# NvideaJetsonPeripherals.net
KiCad netlist of a schematic drawn in Altium Designer
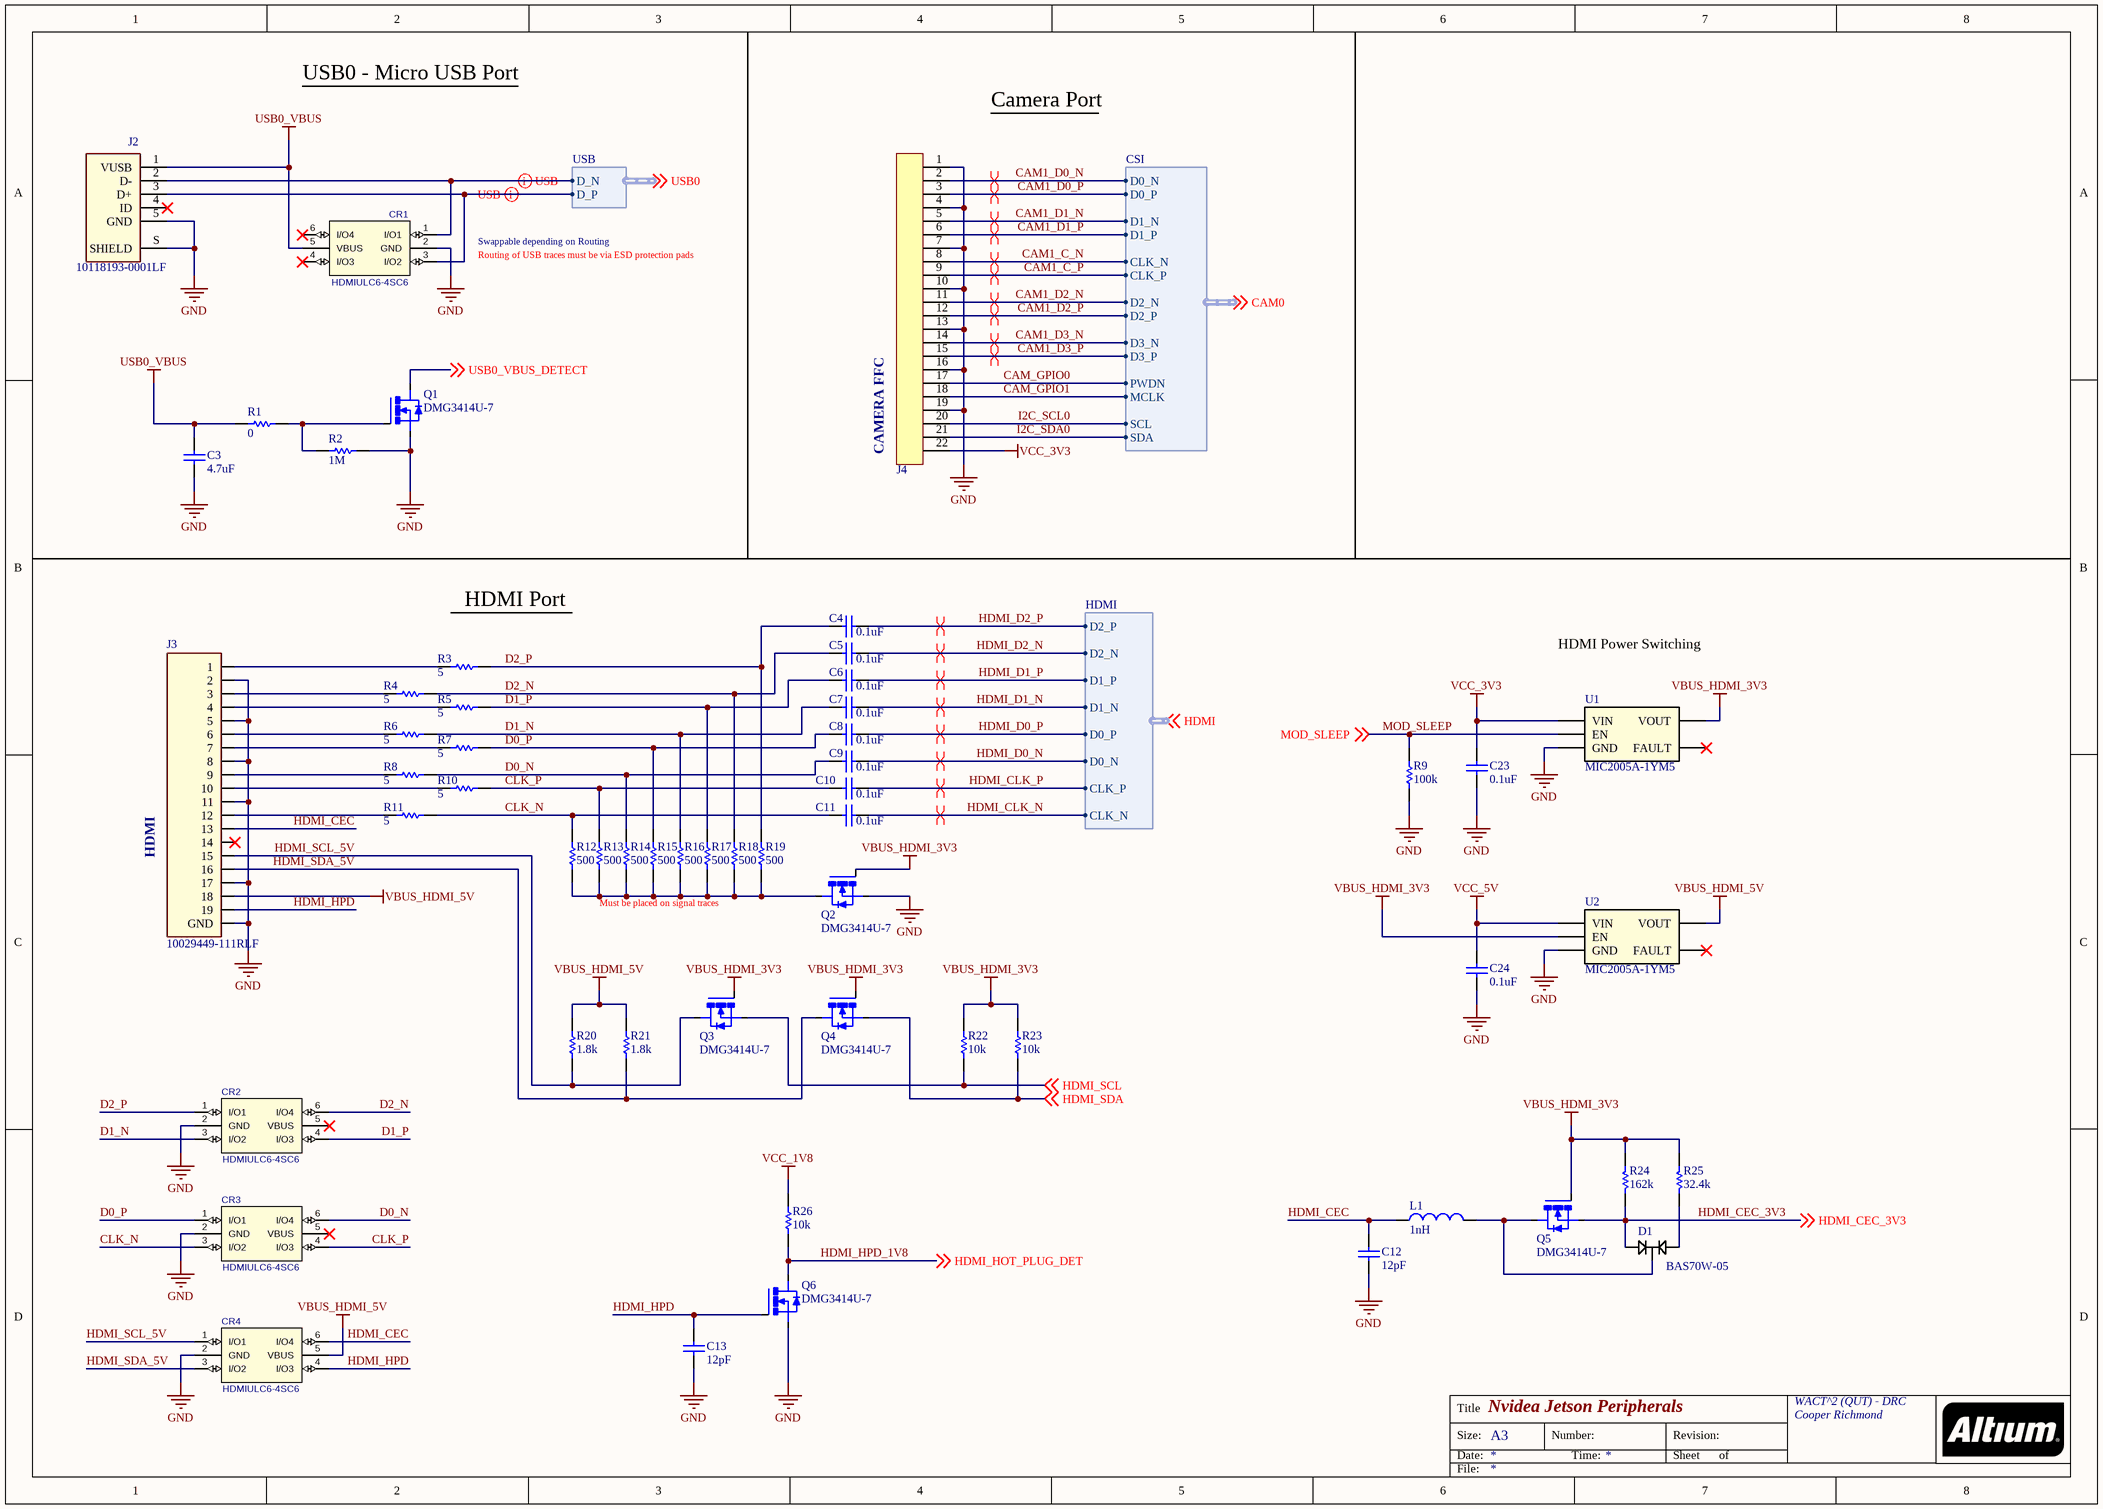
[diagram p0: NvideaJetsonPeripherals.SchDoc]

(export (version "E")
  (design (tool "Eeschema 10.0.6"))
  (components
    (comp (ref "C3")
      (value "4.7uF")
      (footprint "CASE-A")
      (description "=Description")
      (fields (field (name "Comment") "CAP"))
      (libsource (lib "DRClib") (part "CAP"))
    )
    (comp (ref "C4")
      (value "0.1uF")
      (footprint "C0402")
      (description "=Description")
      (fields (field (name "Comment") "CAP"))
      (libsource (lib "DRClib") (part "CAP"))
    )
    (comp (ref "C5")
      (value "0.1uF")
      (footprint "C0402")
      (description "=Description")
      (fields (field (name "Comment") "CAP"))
      (libsource (lib "DRClib") (part "CAP"))
    )
    (comp (ref "C6")
      (value "0.1uF")
      (footprint "C0402")
      (description "=Description")
      (fields (field (name "Comment") "CAP"))
      (libsource (lib "DRClib") (part "CAP"))
    )
    (comp (ref "C7")
      (value "0.1uF")
      (footprint "C0402")
      (description "=Description")
      (fields (field (name "Comment") "CAP"))
      (libsource (lib "DRClib") (part "CAP"))
    )
    (comp (ref "C8")
      (value "0.1uF")
      (footprint "C0402")
      (description "=Description")
      (fields (field (name "Comment") "CAP"))
      (libsource (lib "DRClib") (part "CAP"))
    )
    (comp (ref "C9")
      (value "0.1uF")
      (footprint "C0402")
      (description "=Description")
      (fields (field (name "Comment") "CAP"))
      (libsource (lib "DRClib") (part "CAP"))
    )
    (comp (ref "C10")
      (value "0.1uF")
      (footprint "C0402")
      (description "=Description")
      (fields (field (name "Comment") "CAP"))
      (libsource (lib "DRClib") (part "CAP"))
    )
    (comp (ref "C11")
      (value "0.1uF")
      (footprint "C0402")
      (description "=Description")
      (fields (field (name "Comment") "CAP"))
      (libsource (lib "DRClib") (part "CAP"))
    )
    (comp (ref "C12")
      (value "12pF")
      (footprint "C0402")
      (description "=Description")
      (fields (field (name "Comment") "CAP"))
      (libsource (lib "DRClib") (part "CAP"))
    )
    (comp (ref "C13")
      (value "12pF")
      (footprint "C0402")
      (description "=Description")
      (fields (field (name "Comment") "CAP"))
      (libsource (lib "DRClib") (part "CAP"))
    )
    (comp (ref "C23")
      (value "0.1uF")
      (footprint "C0402")
      (description "=Description")
      (fields (field (name "Comment") "CAP"))
      (libsource (lib "DRClib") (part "CAP"))
    )
    (comp (ref "C24")
      (value "0.1uF")
      (footprint "C0402")
      (description "=Description")
      (fields (field (name "Comment") "CAP"))
      (libsource (lib "DRClib") (part "CAP"))
    )
    (comp (ref "CR1")
      (value "HDMIULC6-4SC6")
      (footprint "SOT23-6L")
      (libsource (lib "") (part "HDMIULC6-4SC6_1"))
    )
    (comp (ref "CR2")
      (value "HDMIULC6-4SC6")
      (footprint "SOT23-6L")
      (libsource (lib "DRClib") (part "HDMIULC6-4SC6"))
    )
    (comp (ref "CR3")
      (value "HDMIULC6-4SC6")
      (footprint "SOT23-6L")
      (libsource (lib "DRClib") (part "HDMIULC6-4SC6"))
    )
    (comp (ref "CR4")
      (value "HDMIULC6-4SC6")
      (footprint "SOT23-6L")
      (libsource (lib "DRClib") (part "HDMIULC6-4SC6"))
    )
    (comp (ref "D1")
      (value "BAS70W-05")
      (footprint "SOT323-3")
      (description "SURFACE MOUNT SCHOTTKY BARRIER DIODE")
      (libsource (lib "DRClib") (part "BAS70W-05"))
    )
    (comp (ref "J2")
      (value "10118193-0001LF")
      (footprint "10118193-0001LF")
      (description "Single Port 5 Contact Shielded SMT MICRO USB B-Type Receptacle")
      (fields (field (name "MF") "Amphenol ICC") (field (name "DIGI-KEY_PART_NUMBER") "609-4616-1-ND"))
      (libsource (lib "DRClib") (part "10118193-0001LF"))
    )
    (comp (ref "J3")
      (value "10029449-111RLF")
      (footprint "10029449-111RLF")
      (description "CONN RCPT 1.4 HDMI 19POS R/A")
      (libsource (lib "DRClib") (part "10029449-111RLF"))
    )
    (comp (ref "J4")
      (value "5019512210")
      (footprint "5019512210")
      (description "FFC 22 POS VERT")
      (libsource (lib "Header") (part "HDR_1x22"))
    )
    (comp (ref "L1")
      (value "1nH")
      (footprint "L0402")
      (description "=Description")
      (fields (field (name "Comment") "IND"))
      (libsource (lib "DRClib") (part "IND"))
    )
    (comp (ref "Q1")
      (value "DMG3414U-7")
      (footprint "SOT23-3")
      (description "=Description")
      (libsource (lib "") (part "MOSFET_N_GSD_1"))
    )
    (comp (ref "Q2")
      (value "DMG3414U-7")
      (footprint "SOT23-3")
      (description "=Description")
      (libsource (lib "DRClib") (part "MOSFET_N_GSD"))
    )
    (comp (ref "Q3")
      (value "DMG3414U-7")
      (footprint "SOT23-3")
      (description "=Description")
      (libsource (lib "DRClib") (part "MOSFET_N_GSD"))
    )
    (comp (ref "Q4")
      (value "DMG3414U-7")
      (footprint "SOT23-3")
      (description "=Description")
      (libsource (lib "DRClib") (part "MOSFET_N_GSD"))
    )
    (comp (ref "Q5")
      (value "DMG3414U-7")
      (footprint "SOT23-3")
      (description "N Channel MOSFET, SOT23")
      (libsource (lib "DRClib") (part "MOSFET_N_GSD"))
    )
    (comp (ref "Q6")
      (value "DMG3414U-7")
      (footprint "SOT23-3")
      (description "N Channel MOSFET, SOT23")
      (libsource (lib "") (part "MOSFET_N_GSD_1"))
    )
    (comp (ref "R1")
      (value "0")
      (footprint "R0402")
      (description "=Description")
      (fields (field (name "Comment") "RES"))
      (libsource (lib "DRClib") (part "RES"))
    )
    (comp (ref "R2")
      (value "1M")
      (footprint "R0402")
      (description "=Description")
      (fields (field (name "Comment") "RES"))
      (libsource (lib "DRClib") (part "RES"))
    )
    (comp (ref "R3")
      (value "5")
      (footprint "R0402")
      (description "=Description")
      (fields (field (name "Comment") "RES"))
      (libsource (lib "DRClib") (part "RES"))
    )
    (comp (ref "R4")
      (value "5")
      (footprint "R0402")
      (description "=Description")
      (fields (field (name "Comment") "RES"))
      (libsource (lib "DRClib") (part "RES"))
    )
    (comp (ref "R5")
      (value "5")
      (footprint "R0402")
      (description "=Description")
      (fields (field (name "Comment") "RES"))
      (libsource (lib "DRClib") (part "RES"))
    )
    (comp (ref "R6")
      (value "5")
      (footprint "R0402")
      (description "=Description")
      (fields (field (name "Comment") "RES"))
      (libsource (lib "DRClib") (part "RES"))
    )
    (comp (ref "R7")
      (value "5")
      (footprint "R0402")
      (description "=Description")
      (fields (field (name "Comment") "RES"))
      (libsource (lib "DRClib") (part "RES"))
    )
    (comp (ref "R8")
      (value "5")
      (footprint "R0402")
      (description "=Description")
      (fields (field (name "Comment") "RES"))
      (libsource (lib "DRClib") (part "RES"))
    )
    (comp (ref "R9")
      (value "100k")
      (footprint "R0402")
      (description "=Description")
      (fields (field (name "Comment") "RES"))
      (libsource (lib "DRClib") (part "RES"))
    )
    (comp (ref "R10")
      (value "5")
      (footprint "R0402")
      (description "=Description")
      (fields (field (name "Comment") "RES"))
      (libsource (lib "DRClib") (part "RES"))
    )
    (comp (ref "R11")
      (value "5")
      (footprint "R0402")
      (description "=Description")
      (fields (field (name "Comment") "RES"))
      (libsource (lib "DRClib") (part "RES"))
    )
    (comp (ref "R12")
      (value "500")
      (footprint "R0402")
      (description "=Description")
      (fields (field (name "Comment") "RES"))
      (libsource (lib "DRClib") (part "RES"))
    )
    (comp (ref "R13")
      (value "500")
      (footprint "R0402")
      (description "=Description")
      (fields (field (name "Comment") "RES"))
      (libsource (lib "DRClib") (part "RES"))
    )
    (comp (ref "R14")
      (value "500")
      (footprint "R0402")
      (description "=Description")
      (fields (field (name "Comment") "RES"))
      (libsource (lib "DRClib") (part "RES"))
    )
    (comp (ref "R15")
      (value "500")
      (footprint "R0402")
      (description "=Description")
      (fields (field (name "Comment") "RES"))
      (libsource (lib "DRClib") (part "RES"))
    )
    (comp (ref "R16")
      (value "500")
      (footprint "R0402")
      (description "=Description")
      (fields (field (name "Comment") "RES"))
      (libsource (lib "DRClib") (part "RES"))
    )
    (comp (ref "R17")
      (value "500")
      (footprint "R0402")
      (description "=Description")
      (fields (field (name "Comment") "RES"))
      (libsource (lib "DRClib") (part "RES"))
    )
    (comp (ref "R18")
      (value "500")
      (footprint "R0402")
      (description "=Description")
      (fields (field (name "Comment") "RES"))
      (libsource (lib "DRClib") (part "RES"))
    )
    (comp (ref "R19")
      (value "500")
      (footprint "R0402")
      (description "=Description")
      (fields (field (name "Comment") "RES"))
      (libsource (lib "DRClib") (part "RES"))
    )
    (comp (ref "R20")
      (value "1.8k")
      (footprint "R0402")
      (description "=Description")
      (fields (field (name "Comment") "RES"))
      (libsource (lib "DRClib") (part "RES"))
    )
    (comp (ref "R21")
      (value "1.8k")
      (footprint "R0402")
      (description "=Description")
      (fields (field (name "Comment") "RES"))
      (libsource (lib "DRClib") (part "RES"))
    )
    (comp (ref "R22")
      (value "10k")
      (footprint "R0402")
      (description "=Description")
      (fields (field (name "Comment") "RES"))
      (libsource (lib "DRClib") (part "RES"))
    )
    (comp (ref "R23")
      (value "10k")
      (footprint "R0402")
      (description "=Description")
      (fields (field (name "Comment") "RES"))
      (libsource (lib "DRClib") (part "RES"))
    )
    (comp (ref "R24")
      (value "162k")
      (footprint "R0402")
      (description "=Description")
      (fields (field (name "Comment") "RES"))
      (libsource (lib "DRClib") (part "RES"))
    )
    (comp (ref "R25")
      (value "32.4k")
      (footprint "R0402")
      (description "=Description")
      (fields (field (name "Comment") "RES"))
      (libsource (lib "DRClib") (part "RES"))
    )
    (comp (ref "R26")
      (value "10k")
      (footprint "R0402")
      (description "=Description")
      (fields (field (name "Comment") "RES"))
      (libsource (lib "DRClib") (part "RES"))
    )
    (comp (ref "U1")
      (value "MIC2005A-1YM5")
      (footprint "SOT23-5")
      (description "Power Switch/Driver 1:1 P-Channel 500mA SOT-23-5")
      (libsource (lib "DRClib") (part "MIC2005A-1YM5"))
    )
    (comp (ref "U2")
      (value "MIC2005A-1YM5")
      (footprint "SOT23-5")
      (description "Power Switch/Driver 1:1 P-Channel 500mA SOT-23-5")
      (libsource (lib "DRClib") (part "MIC2005A-1YM5"))
    )
  )
  (nets
    (net (code "1") (name "/CAM1_C_N") (class "Default")
      (node (ref "J4") (pin "8") (pinfunction "8_8") (pintype "passive"))
    )
    (net (code "2") (name "/CAM1_C_P") (class "Default")
      (node (ref "J4") (pin "9") (pinfunction "9_9") (pintype "passive"))
    )
    (net (code "3") (name "/CAM1_D0_N") (class "Default")
      (node (ref "J4") (pin "2") (pinfunction "2_2") (pintype "passive"))
    )
    (net (code "4") (name "/CAM1_D0_P") (class "Default")
      (node (ref "J4") (pin "3") (pinfunction "3_3") (pintype "passive"))
    )
    (net (code "5") (name "/CAM1_D1_N") (class "Default")
      (node (ref "J4") (pin "5") (pinfunction "5_5") (pintype "passive"))
    )
    (net (code "6") (name "/CAM1_D1_P") (class "Default")
      (node (ref "J4") (pin "6") (pinfunction "6_6") (pintype "passive"))
    )
    (net (code "7") (name "/CAM1_D2_N") (class "Default")
      (node (ref "J4") (pin "11") (pinfunction "11_11") (pintype "passive"))
    )
    (net (code "8") (name "/CAM1_D2_P") (class "Default")
      (node (ref "J4") (pin "12") (pinfunction "12_12") (pintype "passive"))
    )
    (net (code "9") (name "/CAM1_D3_N") (class "Default")
      (node (ref "J4") (pin "14") (pinfunction "14_14") (pintype "passive"))
    )
    (net (code "10") (name "/CAM1_D3_P") (class "Default")
      (node (ref "J4") (pin "15") (pinfunction "15_15") (pintype "passive"))
    )
    (net (code "11") (name "/CAM_GPIO0") (class "Default")
      (node (ref "J4") (pin "17") (pinfunction "17_17") (pintype "passive"))
    )
    (net (code "12") (name "/CAM_GPIO1") (class "Default")
      (node (ref "J4") (pin "18") (pinfunction "18_18") (pintype "passive"))
    )
    (net (code "13") (name "/CLK_N") (class "Default")
      (node (ref "C11") (pin "1") (pinfunction "1_1") (pintype "passive"))
      (node (ref "CR3") (pin "3") (pinfunction "I/O2_3") (pintype "bidirectional"))
      (node (ref "R11") (pin "2") (pinfunction "2_2") (pintype "passive"))
      (node (ref "R12") (pin "1") (pinfunction "1_1") (pintype "passive"))
    )
    (net (code "14") (name "/CLK_P") (class "Default")
      (node (ref "C10") (pin "1") (pinfunction "1_1") (pintype "passive"))
      (node (ref "CR3") (pin "4") (pinfunction "I/O3_4") (pintype "bidirectional"))
      (node (ref "R10") (pin "2") (pinfunction "2_2") (pintype "passive"))
      (node (ref "R13") (pin "1") (pinfunction "1_1") (pintype "passive"))
    )
    (net (code "15") (name "/D0_N") (class "Default")
      (node (ref "C9") (pin "1") (pinfunction "1_1") (pintype "passive"))
      (node (ref "CR3") (pin "6") (pinfunction "I/O4_6") (pintype "bidirectional"))
      (node (ref "R14") (pin "1") (pinfunction "1_1") (pintype "passive"))
      (node (ref "R8") (pin "2") (pinfunction "2_2") (pintype "passive"))
    )
    (net (code "16") (name "/D0_P") (class "Default")
      (node (ref "C8") (pin "1") (pinfunction "1_1") (pintype "passive"))
      (node (ref "CR3") (pin "1") (pinfunction "I/O1_1") (pintype "bidirectional"))
      (node (ref "R15") (pin "1") (pinfunction "1_1") (pintype "passive"))
      (node (ref "R7") (pin "2") (pinfunction "2_2") (pintype "passive"))
    )
    (net (code "17") (name "/D1_N") (class "Default")
      (node (ref "C7") (pin "1") (pinfunction "1_1") (pintype "passive"))
      (node (ref "CR2") (pin "3") (pinfunction "I/O2_3") (pintype "bidirectional"))
      (node (ref "R16") (pin "1") (pinfunction "1_1") (pintype "passive"))
      (node (ref "R6") (pin "2") (pinfunction "2_2") (pintype "passive"))
    )
    (net (code "18") (name "/D1_P") (class "Default")
      (node (ref "C6") (pin "1") (pinfunction "1_1") (pintype "passive"))
      (node (ref "CR2") (pin "4") (pinfunction "I/O3_4") (pintype "bidirectional"))
      (node (ref "R17") (pin "1") (pinfunction "1_1") (pintype "passive"))
      (node (ref "R5") (pin "2") (pinfunction "2_2") (pintype "passive"))
    )
    (net (code "19") (name "/D2_N") (class "Default")
      (node (ref "C5") (pin "1") (pinfunction "1_1") (pintype "passive"))
      (node (ref "CR2") (pin "6") (pinfunction "I/O4_6") (pintype "bidirectional"))
      (node (ref "R18") (pin "1") (pinfunction "1_1") (pintype "passive"))
      (node (ref "R4") (pin "2") (pinfunction "2_2") (pintype "passive"))
    )
    (net (code "20") (name "/D2_P") (class "Default")
      (node (ref "C4") (pin "1") (pinfunction "1_1") (pintype "passive"))
      (node (ref "CR2") (pin "1") (pinfunction "I/O1_1") (pintype "bidirectional"))
      (node (ref "R19") (pin "1") (pinfunction "1_1") (pintype "passive"))
      (node (ref "R3") (pin "2") (pinfunction "2_2") (pintype "passive"))
    )
    (net (code "21") (name "/HDMI_CEC") (class "Default")
      (node (ref "C12") (pin "1") (pinfunction "1_1") (pintype "passive"))
      (node (ref "CR4") (pin "6") (pinfunction "I/O4_6") (pintype "bidirectional"))
      (node (ref "J3") (pin "13") (pinfunction "13_13") (pintype "passive"))
      (node (ref "L1") (pin "2") (pinfunction "2_2") (pintype "passive"))
    )
    (net (code "22") (name "/HDMI_CLK_N") (class "Default")
      (node (ref "C11") (pin "2") (pinfunction "2_2") (pintype "passive"))
    )
    (net (code "23") (name "/HDMI_CLK_P") (class "Default")
      (node (ref "C10") (pin "2") (pinfunction "2_2") (pintype "passive"))
    )
    (net (code "24") (name "/HDMI_D0_N") (class "Default")
      (node (ref "C9") (pin "2") (pinfunction "2_2") (pintype "passive"))
    )
    (net (code "25") (name "/HDMI_D0_P") (class "Default")
      (node (ref "C8") (pin "2") (pinfunction "2_2") (pintype "passive"))
    )
    (net (code "26") (name "/HDMI_D1_N") (class "Default")
      (node (ref "C7") (pin "2") (pinfunction "2_2") (pintype "passive"))
    )
    (net (code "27") (name "/HDMI_D1_P") (class "Default")
      (node (ref "C6") (pin "2") (pinfunction "2_2") (pintype "passive"))
    )
    (net (code "28") (name "/HDMI_D2_N") (class "Default")
      (node (ref "C5") (pin "2") (pinfunction "2_2") (pintype "passive"))
    )
    (net (code "29") (name "/HDMI_D2_P") (class "Default")
      (node (ref "C4") (pin "2") (pinfunction "2_2") (pintype "passive"))
    )
    (net (code "30") (name "/HDMI_HPD") (class "Default")
      (node (ref "C13") (pin "1") (pinfunction "1_1") (pintype "passive"))
      (node (ref "CR4") (pin "4") (pinfunction "I/O3_4") (pintype "bidirectional"))
      (node (ref "J3") (pin "19") (pinfunction "19_19") (pintype "passive"))
      (node (ref "Q6") (pin "1") (pinfunction "G_1") (pintype "passive"))
    )
    (net (code "31") (name "/HDMI_SCL_5V") (class "Default")
      (node (ref "CR4") (pin "1") (pinfunction "I/O1_1") (pintype "bidirectional"))
      (node (ref "J3") (pin "15") (pinfunction "15_15") (pintype "passive"))
      (node (ref "Q3") (pin "3") (pinfunction "D_3") (pintype "passive"))
      (node (ref "R20") (pin "2") (pinfunction "2_2") (pintype "passive"))
    )
    (net (code "32") (name "/HDMI_SDA_5V") (class "Default")
      (node (ref "CR4") (pin "3") (pinfunction "I/O2_3") (pintype "bidirectional"))
      (node (ref "J3") (pin "16") (pinfunction "16_16") (pintype "passive"))
      (node (ref "Q4") (pin "3") (pinfunction "D_3") (pintype "passive"))
      (node (ref "R21") (pin "2") (pinfunction "2_2") (pintype "passive"))
    )
    (net (code "33") (name "/I2C_SCL0") (class "Default")
      (node (ref "J4") (pin "20") (pinfunction "20_20") (pintype "passive"))
    )
    (net (code "34") (name "/I2C_SDA0") (class "Default")
      (node (ref "J4") (pin "21") (pinfunction "21_21") (pintype "passive"))
    )
    (net (code "36") (name "GND") (class "Default")
      (node (ref "C12") (pin "2") (pinfunction "2_2") (pintype "passive"))
      (node (ref "C13") (pin "2") (pinfunction "2_2") (pintype "passive"))
      (node (ref "C23") (pin "1") (pinfunction "1_1") (pintype "passive"))
      (node (ref "C24") (pin "1") (pinfunction "1_1") (pintype "passive"))
      (node (ref "C3") (pin "2") (pinfunction "2_2") (pintype "passive"))
      (node (ref "CR1") (pin "2") (pinfunction "GND_2") (pintype "power_in"))
      (node (ref "CR2") (pin "2") (pinfunction "GND_2") (pintype "power_in"))
      (node (ref "CR3") (pin "2") (pinfunction "GND_2") (pintype "power_in"))
      (node (ref "CR4") (pin "2") (pinfunction "GND_2") (pintype "power_in"))
      (node (ref "J2") (pin "5") (pinfunction "GND_5") (pintype "passive"))
      (node (ref "J2") (pin "S") (pinfunction "SHIELD_S") (pintype "passive"))
      (node (ref "J3") (pin "0") (pinfunction "GND_0") (pintype "passive"))
      (node (ref "J3") (pin "11") (pinfunction "11_11") (pintype "passive"))
      (node (ref "J3") (pin "17") (pinfunction "17_17") (pintype "passive"))
      (node (ref "J3") (pin "2") (pinfunction "2_2") (pintype "passive"))
      (node (ref "J3") (pin "5") (pinfunction "5_5") (pintype "passive"))
      (node (ref "J3") (pin "8") (pinfunction "8_8") (pintype "passive"))
      (node (ref "J4") (pin "1") (pinfunction "1_1") (pintype "passive"))
      (node (ref "J4") (pin "10") (pinfunction "10_10") (pintype "passive"))
      (node (ref "J4") (pin "13") (pinfunction "13_13") (pintype "passive"))
      (node (ref "J4") (pin "16") (pinfunction "16_16") (pintype "passive"))
      (node (ref "J4") (pin "19") (pinfunction "19_19") (pintype "passive"))
      (node (ref "J4") (pin "4") (pinfunction "4_4") (pintype "passive"))
      (node (ref "J4") (pin "7") (pinfunction "7_7") (pintype "passive"))
      (node (ref "Q1") (pin "2") (pinfunction "S_2") (pintype "passive"))
      (node (ref "Q2") (pin "2") (pinfunction "S_2") (pintype "passive"))
      (node (ref "Q6") (pin "2") (pinfunction "S_2") (pintype "passive"))
      (node (ref "R2") (pin "1") (pinfunction "1_1") (pintype "passive"))
      (node (ref "R9") (pin "2") (pinfunction "2_2") (pintype "passive"))
      (node (ref "U1") (pin "2") (pinfunction "GND_2") (pintype "passive"))
      (node (ref "U2") (pin "2") (pinfunction "GND_2") (pintype "passive"))
    )
    (net (code "38") (name "HDMI_CEC_3V3") (class "Default")
      (node (ref "D1") (pin "1") (pinfunction "0_1") (pintype "passive"))
      (node (ref "Q5") (pin "2") (pinfunction "S_2") (pintype "passive"))
      (node (ref "R24") (pin "2") (pinfunction "2_2") (pintype "passive"))
    )
    (net (code "39") (name "HDMI_HOT_PLUG_DET") (class "Default")
      (node (ref "Q6") (pin "3") (pinfunction "D_3") (pintype "passive"))
      (node (ref "R26") (pin "2") (pinfunction "2_2") (pintype "passive"))
    )
    (net (code "40") (name "HDMI_SCL") (class "Default")
      (node (ref "Q3") (pin "2") (pinfunction "S_2") (pintype "passive"))
      (node (ref "R22") (pin "2") (pinfunction "2_2") (pintype "passive"))
    )
    (net (code "41") (name "HDMI_SDA") (class "Default")
      (node (ref "Q4") (pin "2") (pinfunction "S_2") (pintype "passive"))
      (node (ref "R23") (pin "2") (pinfunction "2_2") (pintype "passive"))
    )
    (net (code "42") (name "MOD_SLEEP") (class "Default")
      (node (ref "R9") (pin "1") (pinfunction "1_1") (pintype "passive"))
      (node (ref "U1") (pin "3") (pinfunction "EN_3") (pintype "passive"))
    )
    (net (code "43") (name "Net-(CR1-I{slash}O1)") (class "Default")
      (node (ref "CR1") (pin "1") (pinfunction "I/O1_1") (pintype "bidirectional"))
      (node (ref "J2") (pin "2") (pinfunction "D-_2") (pintype "passive"))
    )
    (net (code "44") (name "Net-(CR1-I{slash}O2)") (class "Default")
      (node (ref "CR1") (pin "3") (pinfunction "I/O2_3") (pintype "bidirectional"))
      (node (ref "J2") (pin "3") (pinfunction "D+_3") (pintype "passive"))
    )
    (net (code "45") (name "Net-(D1-0-Pad2)") (class "Default")
      (node (ref "D1") (pin "2") (pinfunction "0_2") (pintype "passive"))
      (node (ref "R25") (pin "2") (pinfunction "2_2") (pintype "passive"))
    )
    (net (code "46") (name "Net-(J3-Pad1)") (class "Default")
      (node (ref "J3") (pin "1") (pinfunction "1_1") (pintype "passive"))
      (node (ref "R3") (pin "1") (pinfunction "1_1") (pintype "passive"))
    )
    (net (code "47") (name "Net-(J3-Pad3)") (class "Default")
      (node (ref "J3") (pin "3") (pinfunction "3_3") (pintype "passive"))
      (node (ref "R4") (pin "1") (pinfunction "1_1") (pintype "passive"))
    )
    (net (code "48") (name "Net-(J3-Pad4)") (class "Default")
      (node (ref "J3") (pin "4") (pinfunction "4_4") (pintype "passive"))
      (node (ref "R5") (pin "1") (pinfunction "1_1") (pintype "passive"))
    )
    (net (code "49") (name "Net-(J3-Pad6)") (class "Default")
      (node (ref "J3") (pin "6") (pinfunction "6_6") (pintype "passive"))
      (node (ref "R6") (pin "1") (pinfunction "1_1") (pintype "passive"))
    )
    (net (code "50") (name "Net-(J3-Pad7)") (class "Default")
      (node (ref "J3") (pin "7") (pinfunction "7_7") (pintype "passive"))
      (node (ref "R7") (pin "1") (pinfunction "1_1") (pintype "passive"))
    )
    (net (code "51") (name "Net-(J3-Pad9)") (class "Default")
      (node (ref "J3") (pin "9") (pinfunction "9_9") (pintype "passive"))
      (node (ref "R8") (pin "1") (pinfunction "1_1") (pintype "passive"))
    )
    (net (code "52") (name "Net-(J3-Pad10)") (class "Default")
      (node (ref "J3") (pin "10") (pinfunction "10_10") (pintype "passive"))
      (node (ref "R10") (pin "1") (pinfunction "1_1") (pintype "passive"))
    )
    (net (code "53") (name "Net-(J3-Pad12)") (class "Default")
      (node (ref "J3") (pin "12") (pinfunction "12_12") (pintype "passive"))
      (node (ref "R11") (pin "1") (pinfunction "1_1") (pintype "passive"))
    )
    (net (code "54") (name "Net-(Q1-G)") (class "Default")
      (node (ref "Q1") (pin "1") (pinfunction "G_1") (pintype "passive"))
      (node (ref "R1") (pin "2") (pinfunction "2_2") (pintype "passive"))
      (node (ref "R2") (pin "2") (pinfunction "2_2") (pintype "passive"))
    )
    (net (code "55") (name "Net-(Q2-D)") (class "Default")
      (node (ref "Q2") (pin "3") (pinfunction "D_3") (pintype "passive"))
      (node (ref "R12") (pin "2") (pinfunction "2_2") (pintype "passive"))
      (node (ref "R13") (pin "2") (pinfunction "2_2") (pintype "passive"))
      (node (ref "R14") (pin "2") (pinfunction "2_2") (pintype "passive"))
      (node (ref "R15") (pin "2") (pinfunction "2_2") (pintype "passive"))
      (node (ref "R16") (pin "2") (pinfunction "2_2") (pintype "passive"))
      (node (ref "R17") (pin "2") (pinfunction "2_2") (pintype "passive"))
      (node (ref "R18") (pin "2") (pinfunction "2_2") (pintype "passive"))
      (node (ref "R19") (pin "2") (pinfunction "2_2") (pintype "passive"))
    )
    (net (code "56") (name "Net-(Q5-D)") (class "Default")
      (node (ref "D1") (pin "3") (pinfunction "0_3") (pintype "passive"))
      (node (ref "L1") (pin "1") (pinfunction "1_1") (pintype "passive"))
      (node (ref "Q5") (pin "3") (pinfunction "D_3") (pintype "passive"))
    )
    (net (code "58") (name "USB0_VBUS") (class "Default")
      (node (ref "C3") (pin "1") (pinfunction "1_1") (pintype "passive"))
      (node (ref "CR1") (pin "5") (pinfunction "VBUS_5") (pintype "power_in"))
      (node (ref "J2") (pin "1") (pinfunction "VUSB_1") (pintype "passive"))
      (node (ref "R1") (pin "1") (pinfunction "1_1") (pintype "passive"))
    )
    (net (code "59") (name "USB0_VBUS_DETECT") (class "Default")
      (node (ref "Q1") (pin "3") (pinfunction "D_3") (pintype "passive"))
    )
    (net (code "60") (name "VBUS_HDMI_3V3") (class "Default")
      (node (ref "Q2") (pin "1") (pinfunction "G_1") (pintype "passive"))
      (node (ref "Q3") (pin "1") (pinfunction "G_1") (pintype "passive"))
      (node (ref "Q4") (pin "1") (pinfunction "G_1") (pintype "passive"))
      (node (ref "Q5") (pin "1") (pinfunction "G_1") (pintype "passive"))
      (node (ref "R22") (pin "1") (pinfunction "1_1") (pintype "passive"))
      (node (ref "R23") (pin "1") (pinfunction "1_1") (pintype "passive"))
      (node (ref "R24") (pin "1") (pinfunction "1_1") (pintype "passive"))
      (node (ref "R25") (pin "1") (pinfunction "1_1") (pintype "passive"))
      (node (ref "U1") (pin "5") (pinfunction "VOUT_5") (pintype "passive"))
      (node (ref "U2") (pin "3") (pinfunction "EN_3") (pintype "passive"))
    )
    (net (code "61") (name "VBUS_HDMI_5V") (class "Default")
      (node (ref "CR4") (pin "5") (pinfunction "VBUS_5") (pintype "power_in"))
      (node (ref "J3") (pin "18") (pinfunction "18_18") (pintype "passive"))
      (node (ref "R20") (pin "1") (pinfunction "1_1") (pintype "passive"))
      (node (ref "R21") (pin "1") (pinfunction "1_1") (pintype "passive"))
      (node (ref "U2") (pin "5") (pinfunction "VOUT_5") (pintype "passive"))
    )
    (net (code "62") (name "VCC_1V8") (class "Default")
      (node (ref "R26") (pin "1") (pinfunction "1_1") (pintype "passive"))
    )
    (net (code "63") (name "VCC_3V3") (class "Default")
      (node (ref "C23") (pin "2") (pinfunction "2_2") (pintype "passive"))
      (node (ref "J4") (pin "22") (pinfunction "22_22") (pintype "passive"))
      (node (ref "U1") (pin "1") (pinfunction "VIN_1") (pintype "passive"))
    )
    (net (code "64") (name "VCC_5V") (class "Default")
      (node (ref "C24") (pin "2") (pinfunction "2_2") (pintype "passive"))
      (node (ref "U2") (pin "1") (pinfunction "VIN_1") (pintype "passive"))
    )
    (net (code "65") (name "unconnected-(CR1-I{slash}O3-Pad4)") (class "Default")
      (node (ref "CR1") (pin "4") (pinfunction "I/O3_4") (pintype "bidirectional+no_connect"))
    )
    (net (code "66") (name "unconnected-(CR1-I{slash}O4-Pad6)") (class "Default")
      (node (ref "CR1") (pin "6") (pinfunction "I/O4_6") (pintype "bidirectional+no_connect"))
    )
    (net (code "67") (name "unconnected-(CR2-VBUS-Pad5)") (class "Default")
      (node (ref "CR2") (pin "5") (pinfunction "VBUS_5") (pintype "power_in+no_connect"))
    )
    (net (code "68") (name "unconnected-(CR3-VBUS-Pad5)") (class "Default")
      (node (ref "CR3") (pin "5") (pinfunction "VBUS_5") (pintype "power_in+no_connect"))
    )
    (net (code "69") (name "unconnected-(J2-ID-Pad4)") (class "Default")
      (node (ref "J2") (pin "4") (pinfunction "ID_4") (pintype "passive+no_connect"))
    )
    (net (code "70") (name "unconnected-(J3-Pad14)") (class "Default")
      (node (ref "J3") (pin "14") (pinfunction "14_14") (pintype "passive+no_connect"))
    )
    (net (code "71") (name "unconnected-(U1-FAULT-Pad4)") (class "Default")
      (node (ref "U1") (pin "4") (pinfunction "FAULT_4") (pintype "passive+no_connect"))
    )
    (net (code "72") (name "unconnected-(U2-FAULT-Pad4)") (class "Default")
      (node (ref "U2") (pin "4") (pinfunction "FAULT_4") (pintype "passive+no_connect"))
    )
  )
)
